# PlantAlarm.net
KiCad netlist of a schematic drawn in EAGLE
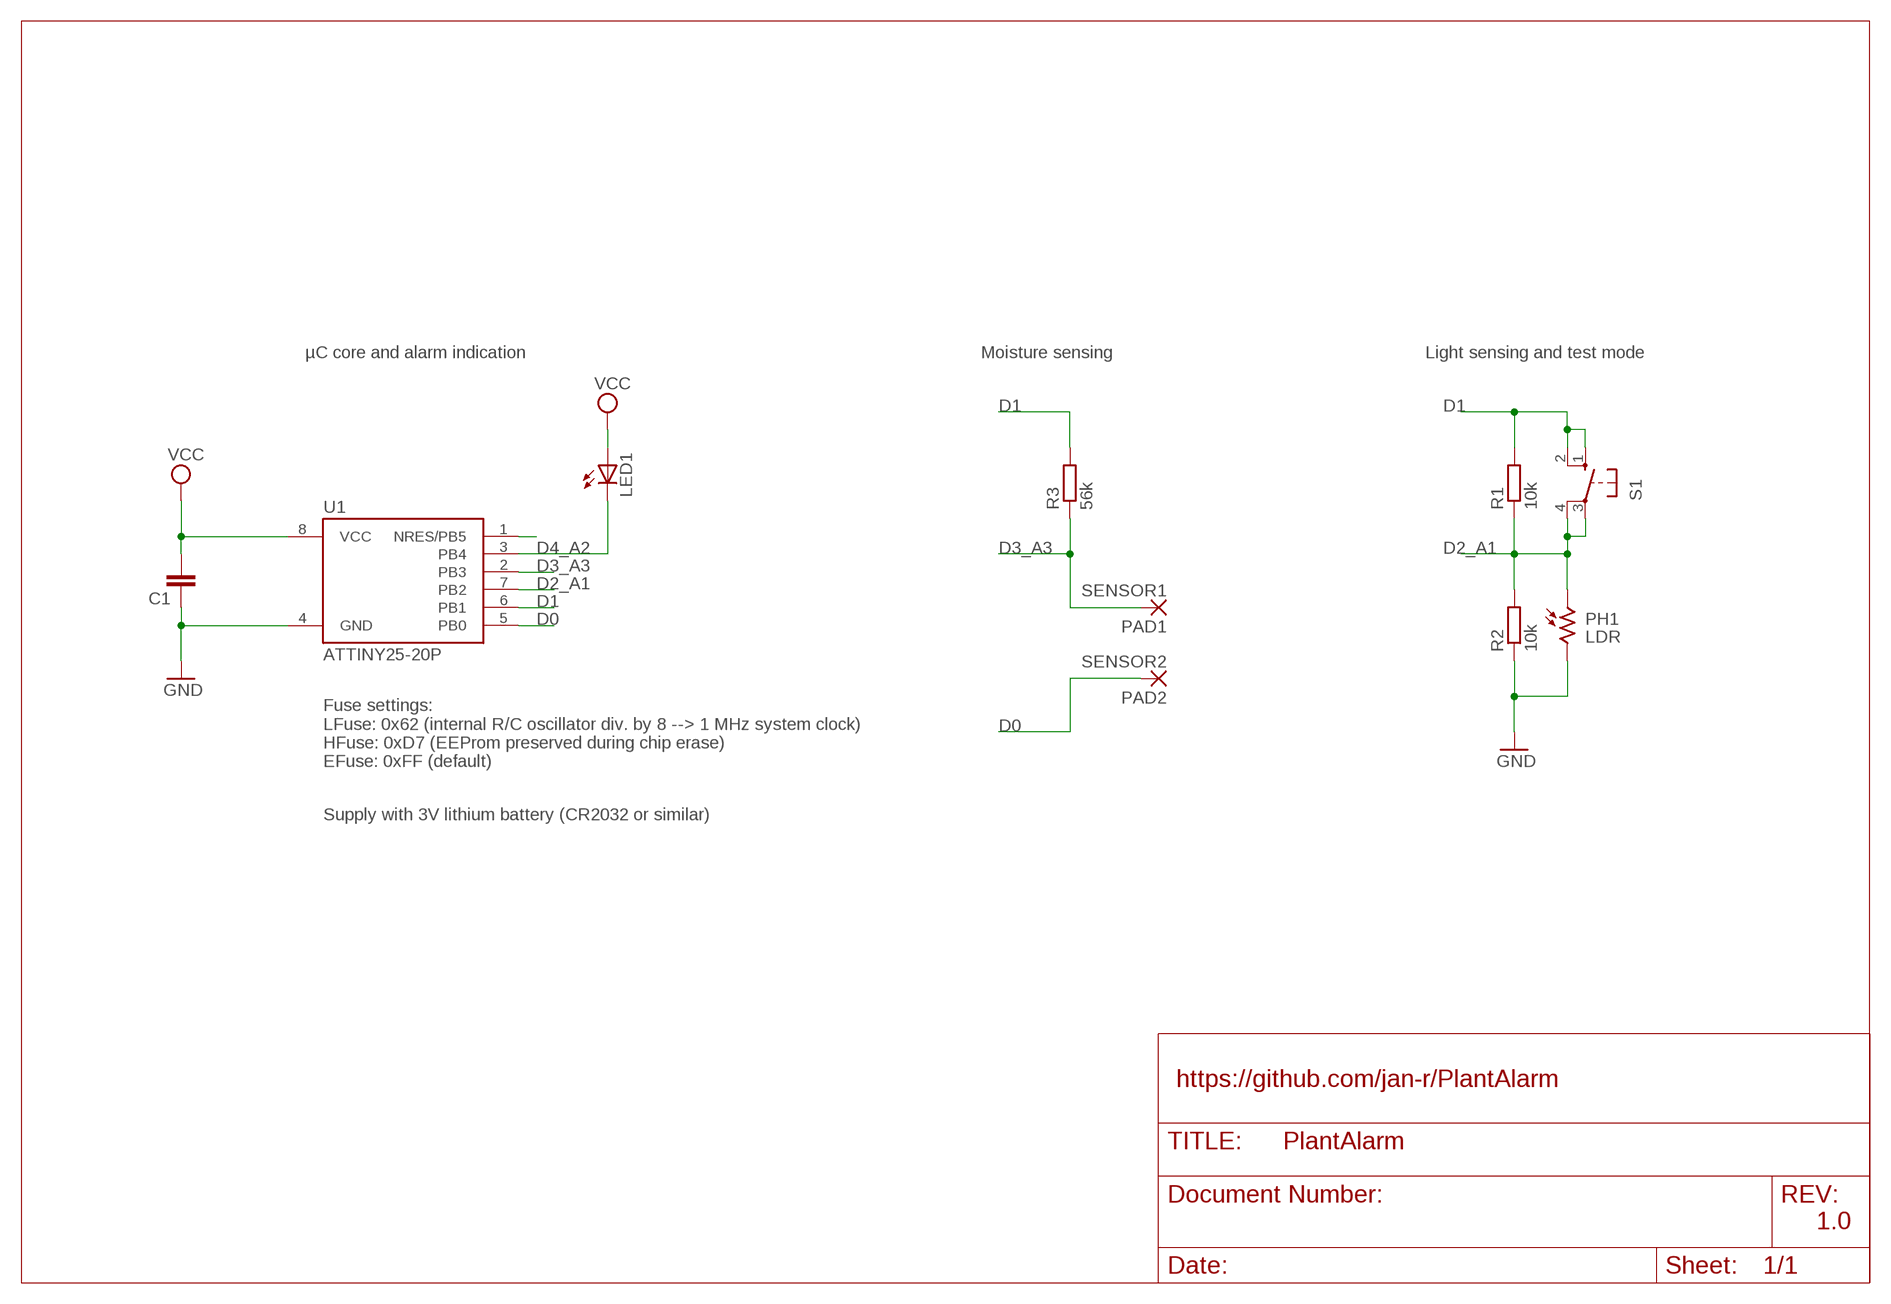
[diagram p0: schematic, sheet 1]

(export (version "E")
  (design (tool "Eeschema 10.0.6"))
  (components
    (comp (ref "C1")
      (value "C-EU025-025X050")
      (footprint "eagle-import:C025-025X050")
      (libsource (lib "eagle-import") (part "C-EU025-025X050"))
    )
    (comp (ref "LED1")
      (value "LED3MM")
      (footprint "eagle-import:LED3MM")
      (libsource (lib "eagle-import") (part "LED3MM"))
    )
    (comp (ref "PAD1")
      (value "SENSOR1")
      (footprint "eagle-import:5-2,5")
      (libsource (lib "eagle-import") (part "WIREPADSMD5-2,5"))
    )
    (comp (ref "PAD2")
      (value "SENSOR2")
      (footprint "eagle-import:5-2,5")
      (libsource (lib "eagle-import") (part "WIREPADSMD5-2,5"))
    )
    (comp (ref "PH1")
      (value "LDR")
      (footprint "eagle-import:M9960")
      (libsource (lib "eagle-import") (part "M9960_11A"))
    )
    (comp (ref "R1")
      (value "10k")
      (footprint "eagle-import:0207_10")
      (libsource (lib "eagle-import") (part "R-EU_0207/10"))
    )
    (comp (ref "R2")
      (value "10k")
      (footprint "eagle-import:0207_10")
      (libsource (lib "eagle-import") (part "R-EU_0207/10"))
    )
    (comp (ref "R3")
      (value "56k")
      (footprint "eagle-import:0207_10")
      (libsource (lib "eagle-import") (part "R-EU_0207/10"))
    )
    (comp (ref "S1")
      (value "10-XX")
      (footprint "eagle-import:B3F-10XX")
      (fields (field (name "MPN") "B3F-1000"))
      (libsource (lib "eagle-import") (part "10-XX"))
    )
    (comp (ref "U1")
      (value "ATTINY25-20P")
      (footprint "eagle-import:PDIP08_300MIL")
      (libsource (lib "eagle-import") (part "ATTINY25P-20"))
    )
  )
  (nets
    (net (code "1") (name "/D0") (class "Default")
      (node (ref "PAD2") (pin "1") (pinfunction "P_1") (pintype "passive"))
      (node (ref "U1") (pin "5") (pinfunction "PB0_5") (pintype "bidirectional"))
    )
    (net (code "2") (name "/D1") (class "Default")
      (node (ref "R1") (pin "2") (pinfunction "2_2") (pintype "passive"))
      (node (ref "R3") (pin "2") (pinfunction "2_2") (pintype "passive"))
      (node (ref "S1") (pin "1") (pinfunction "S_1") (pintype "passive"))
      (node (ref "S1") (pin "2") (pinfunction "S1_2") (pintype "passive"))
      (node (ref "U1") (pin "6") (pinfunction "PB1_6") (pintype "bidirectional"))
    )
    (net (code "3") (name "/D2_A1") (class "Default")
      (node (ref "PH1") (pin "1") (pinfunction "1_1") (pintype "passive"))
      (node (ref "R1") (pin "1") (pinfunction "1_1") (pintype "passive"))
      (node (ref "R2") (pin "2") (pinfunction "2_2") (pintype "passive"))
      (node (ref "S1") (pin "3") (pinfunction "P_3") (pintype "passive"))
      (node (ref "S1") (pin "4") (pinfunction "P1_4") (pintype "passive"))
      (node (ref "U1") (pin "7") (pinfunction "PB2_7") (pintype "bidirectional"))
    )
    (net (code "4") (name "/D3_A3") (class "Default")
      (node (ref "PAD1") (pin "1") (pinfunction "P_1") (pintype "passive"))
      (node (ref "R3") (pin "1") (pinfunction "1_1") (pintype "passive"))
      (node (ref "U1") (pin "2") (pinfunction "PB3_2") (pintype "bidirectional"))
    )
    (net (code "5") (name "/D4_A2") (class "Default")
      (node (ref "LED1") (pin "K") (pinfunction "C_K") (pintype "passive"))
      (node (ref "U1") (pin "3") (pinfunction "PB4_3") (pintype "bidirectional"))
    )
    (net (code "6") (name "GND") (class "Default")
      (node (ref "C1") (pin "1") (pinfunction "1_1") (pintype "passive"))
      (node (ref "PH1") (pin "2") (pinfunction "2_2") (pintype "passive"))
      (node (ref "R2") (pin "1") (pinfunction "1_1") (pintype "passive"))
      (node (ref "U1") (pin "4") (pinfunction "GND_4") (pintype "power_in"))
    )
    (net (code "7") (name "VCC") (class "Default")
      (node (ref "C1") (pin "2") (pinfunction "2_2") (pintype "passive"))
      (node (ref "LED1") (pin "A") (pinfunction "A_A") (pintype "passive"))
      (node (ref "U1") (pin "8") (pinfunction "VCC_8") (pintype "power_in"))
    )
    (net (code "8") (name "unconnected-(U1-NRES{slash}PB5-Pad1)") (class "Default")
      (node (ref "U1") (pin "1") (pinfunction "NRES/PB5_1") (pintype "bidirectional"))
    )
  )
)
